# SC70_SOT23.net
KiCad netlist of a schematic drawn in EAGLE
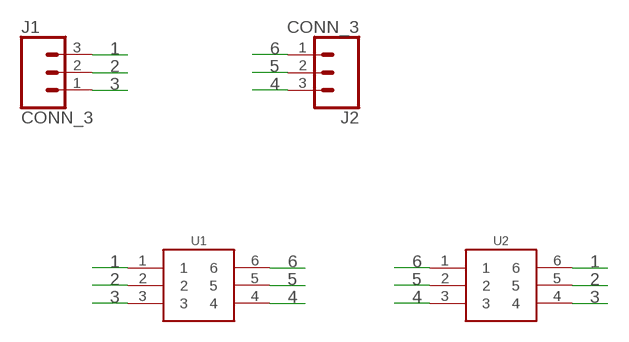
[diagram p0: schematic, sheet 1]

(export (version "E")
  (design (tool "Eeschema 10.0.6"))
  (components
    (comp (ref "J1")
      (value "CONN_3")
      (footprint "eagle-import:1X03")
      (libsource (lib "eagle-import") (part "CONN_3"))
    )
    (comp (ref "J2")
      (value "CONN_3")
      (footprint "eagle-import:1X03")
      (libsource (lib "eagle-import") (part "CONN_3"))
    )
    (comp (ref "U1")
      (value "GEN_6SC-70")
      (footprint "eagle-import:DCK_R-PDSO-G6")
      (libsource (lib "eagle-import") (part "GEN_6SC-70"))
    )
    (comp (ref "U2")
      (value "GEN_6SOT-23")
      (footprint "eagle-import:DDC_R-PDSO-G6")
      (libsource (lib "eagle-import") (part "GEN_6SOT-23"))
    )
  )
  (nets
    (net (code "1") (name "/1") (class "Default")
      (node (ref "J1") (pin "3") (pinfunction "3_3") (pintype "passive"))
      (node (ref "U1") (pin "1") (pinfunction "1_1") (pintype "bidirectional"))
      (node (ref "U2") (pin "6") (pinfunction "6_6") (pintype "bidirectional"))
    )
    (net (code "2") (name "/2") (class "Default")
      (node (ref "J1") (pin "2") (pinfunction "2_2") (pintype "passive"))
      (node (ref "U1") (pin "2") (pinfunction "2_2") (pintype "bidirectional"))
      (node (ref "U2") (pin "5") (pinfunction "5_5") (pintype "bidirectional"))
    )
    (net (code "3") (name "/3") (class "Default")
      (node (ref "J1") (pin "1") (pinfunction "1_1") (pintype "passive"))
      (node (ref "U1") (pin "3") (pinfunction "3_3") (pintype "bidirectional"))
      (node (ref "U2") (pin "4") (pinfunction "4_4") (pintype "bidirectional"))
    )
    (net (code "4") (name "/4") (class "Default")
      (node (ref "J2") (pin "3") (pinfunction "3_3") (pintype "passive"))
      (node (ref "U1") (pin "4") (pinfunction "4_4") (pintype "bidirectional"))
      (node (ref "U2") (pin "3") (pinfunction "3_3") (pintype "bidirectional"))
    )
    (net (code "5") (name "/5") (class "Default")
      (node (ref "J2") (pin "2") (pinfunction "2_2") (pintype "passive"))
      (node (ref "U1") (pin "5") (pinfunction "5_5") (pintype "bidirectional"))
      (node (ref "U2") (pin "2") (pinfunction "2_2") (pintype "bidirectional"))
    )
    (net (code "6") (name "/6") (class "Default")
      (node (ref "J2") (pin "1") (pinfunction "1_1") (pintype "passive"))
      (node (ref "U1") (pin "6") (pinfunction "6_6") (pintype "bidirectional"))
      (node (ref "U2") (pin "1") (pinfunction "1_1") (pintype "bidirectional"))
    )
  )
)
